# design.net
KiCad netlist of a schematic drawn in EAGLE
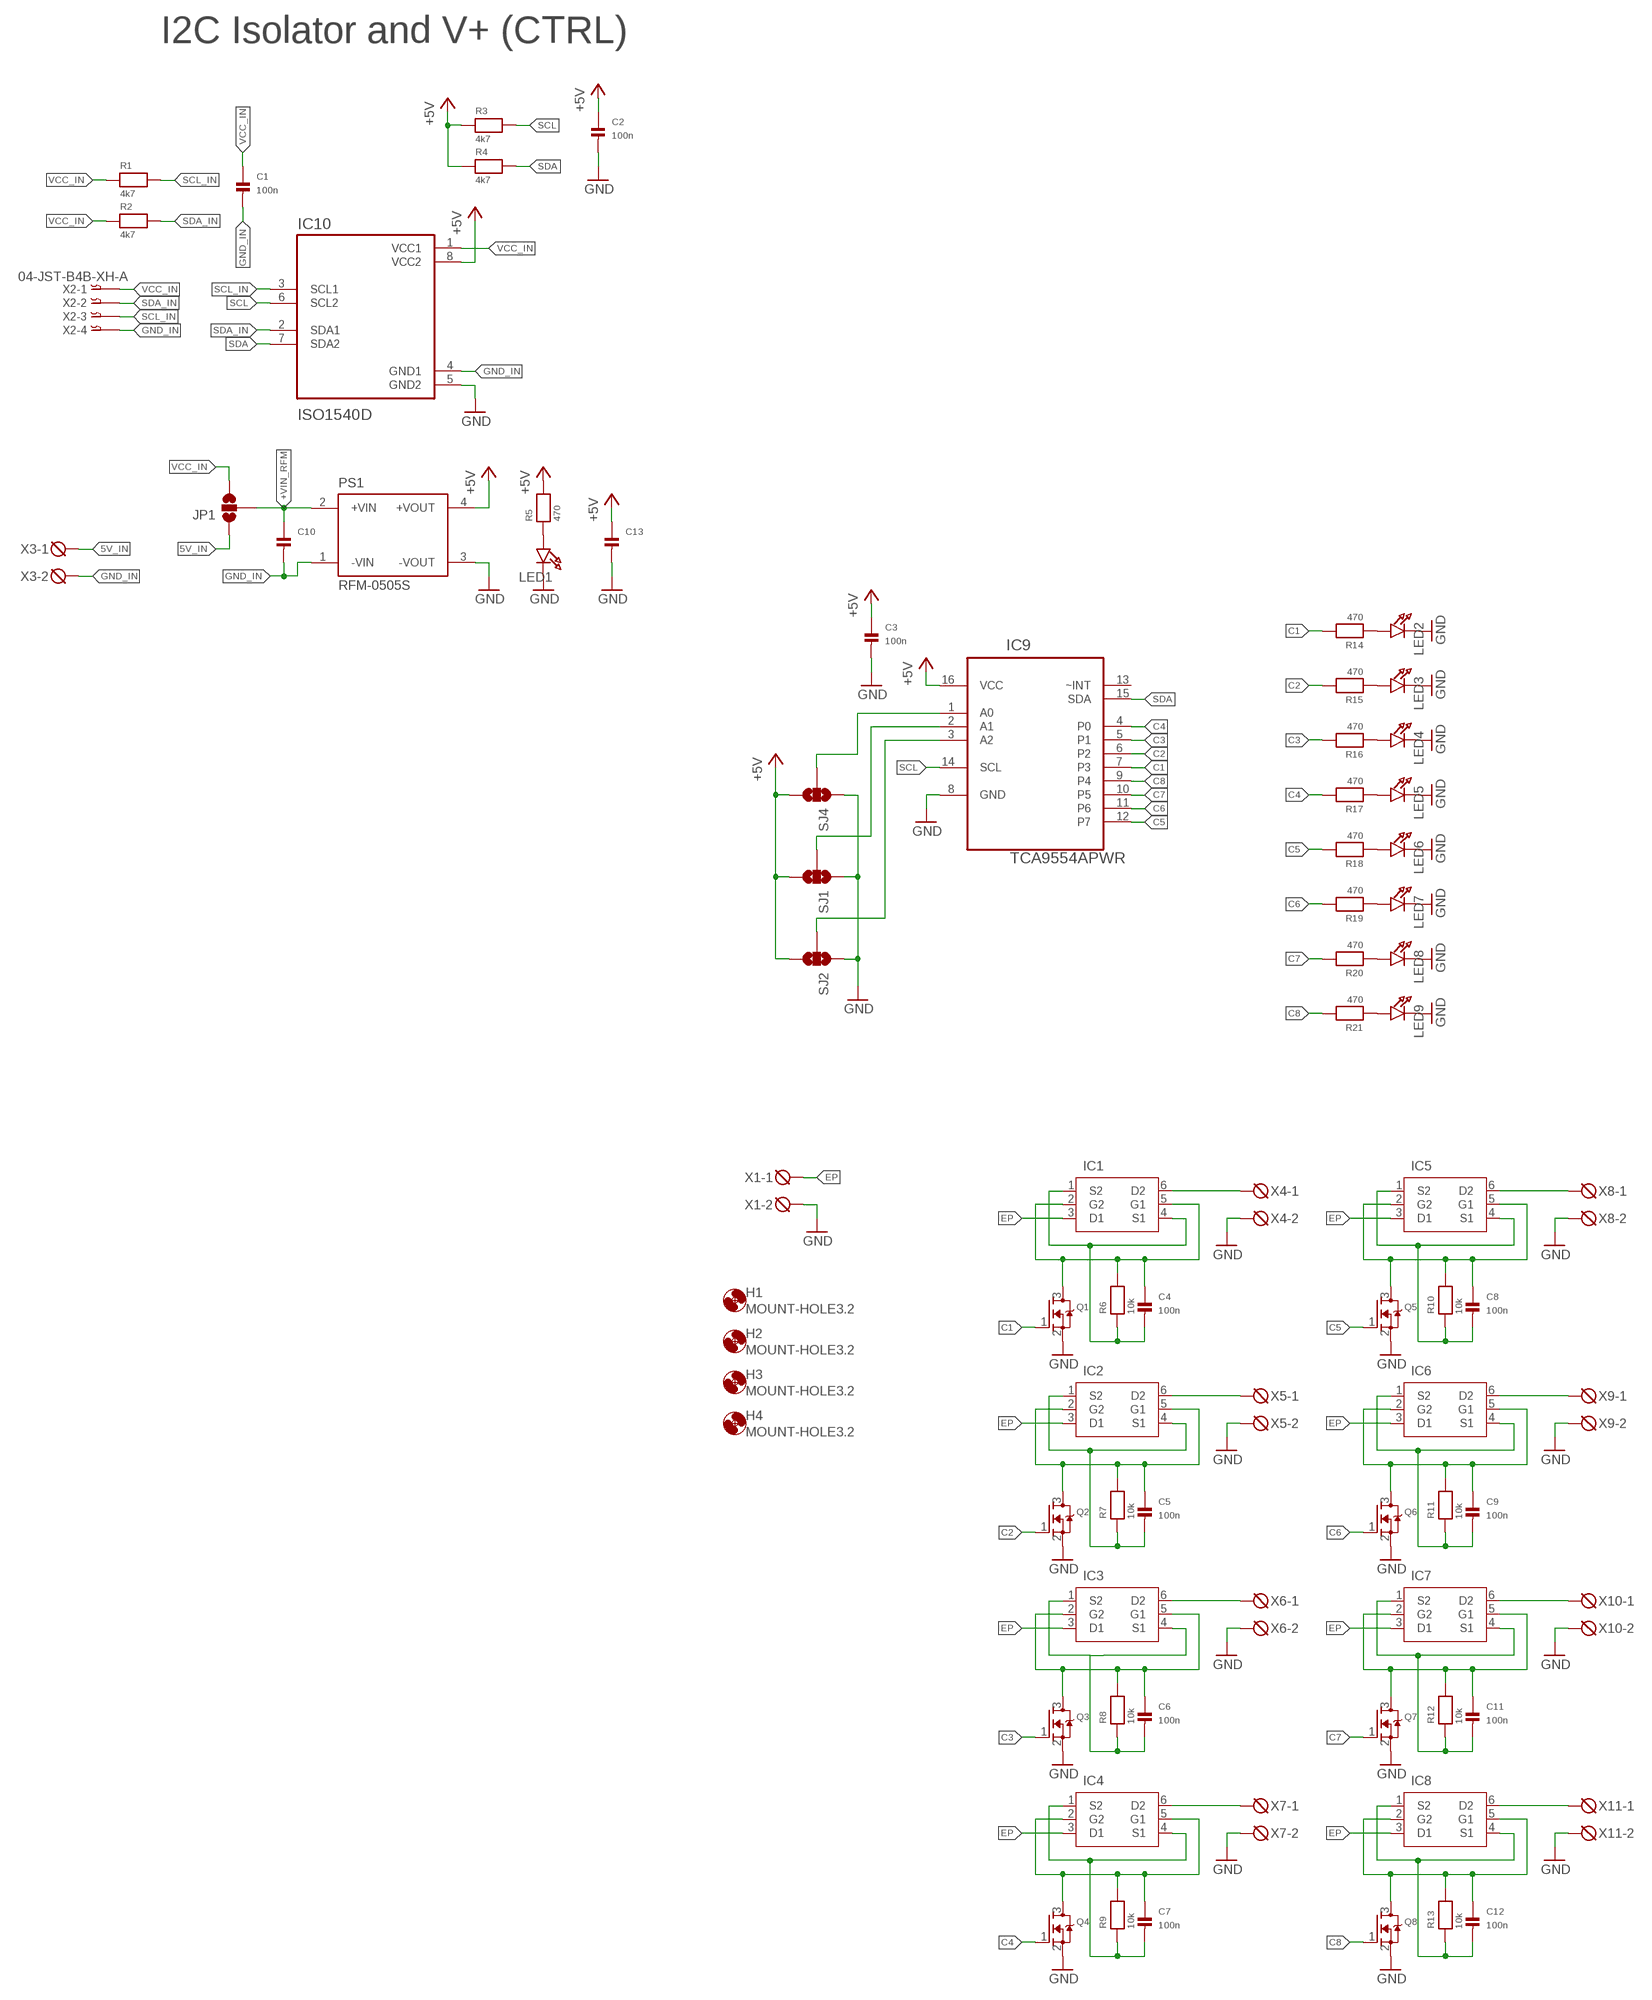
[diagram p0: schematic, sheet 1]

(export (version "E")
  (design (tool "Eeschema 10.0.6"))
  (components
    (comp (ref "C1")
      (value "100n")
      (footprint "eagle-import:0603")
      (libsource (lib "eagle-import") (part "CAP_CERAMIC0603"))
    )
    (comp (ref "C2")
      (value "100n")
      (footprint "eagle-import:0603")
      (libsource (lib "eagle-import") (part "CAP_CERAMIC0603"))
    )
    (comp (ref "C3")
      (value "100n")
      (footprint "eagle-import:0603")
      (libsource (lib "eagle-import") (part "CAP_CERAMIC0603"))
    )
    (comp (ref "C4")
      (value "100n")
      (footprint "eagle-import:0603")
      (libsource (lib "eagle-import") (part "CAP_CERAMIC0603"))
    )
    (comp (ref "C5")
      (value "100n")
      (footprint "eagle-import:0603")
      (libsource (lib "eagle-import") (part "CAP_CERAMIC0603"))
    )
    (comp (ref "C6")
      (value "100n")
      (footprint "eagle-import:0603")
      (libsource (lib "eagle-import") (part "CAP_CERAMIC0603"))
    )
    (comp (ref "C7")
      (value "100n")
      (footprint "eagle-import:0603")
      (libsource (lib "eagle-import") (part "CAP_CERAMIC0603"))
    )
    (comp (ref "C8")
      (value "100n")
      (footprint "eagle-import:0603")
      (libsource (lib "eagle-import") (part "CAP_CERAMIC0603"))
    )
    (comp (ref "C9")
      (value "100n")
      (footprint "eagle-import:0603")
      (libsource (lib "eagle-import") (part "CAP_CERAMIC0603"))
    )
    (comp (ref "C10")
      (value "CAP_CERAMIC0805")
      (footprint "eagle-import:0805")
      (libsource (lib "eagle-import") (part "CAP_CERAMIC0805"))
    )
    (comp (ref "C11")
      (value "100n")
      (footprint "eagle-import:0603")
      (libsource (lib "eagle-import") (part "CAP_CERAMIC0603"))
    )
    (comp (ref "C12")
      (value "100n")
      (footprint "eagle-import:0603")
      (libsource (lib "eagle-import") (part "CAP_CERAMIC0603"))
    )
    (comp (ref "C13")
      (value "CAP_CERAMIC0805")
      (footprint "eagle-import:0805")
      (libsource (lib "eagle-import") (part "CAP_CERAMIC0805"))
    )
    (comp (ref "H1")
      (value "MOUNT-HOLE3.2")
      (footprint "eagle-import:3,2")
      (libsource (lib "eagle-import") (part "MOUNT-HOLE3.2"))
    )
    (comp (ref "H2")
      (value "MOUNT-HOLE3.2")
      (footprint "eagle-import:3,2")
      (libsource (lib "eagle-import") (part "MOUNT-HOLE3.2"))
    )
    (comp (ref "H3")
      (value "MOUNT-HOLE3.2")
      (footprint "eagle-import:3,2")
      (libsource (lib "eagle-import") (part "MOUNT-HOLE3.2"))
    )
    (comp (ref "H4")
      (value "MOUNT-HOLE3.2")
      (footprint "eagle-import:3,2")
      (libsource (lib "eagle-import") (part "MOUNT-HOLE3.2"))
    )
    (comp (ref "IC1")
      (value "DMP2200UDW")
      (footprint "eagle-import:SOT65P210X110-6N")
      (libsource (lib "eagle-import") (part "DMP2200UDW"))
    )
    (comp (ref "IC2")
      (value "DMP2200UDW")
      (footprint "eagle-import:SOT65P210X110-6N")
      (libsource (lib "eagle-import") (part "DMP2200UDW"))
    )
    (comp (ref "IC3")
      (value "DMP2200UDW")
      (footprint "eagle-import:SOT65P210X110-6N")
      (libsource (lib "eagle-import") (part "DMP2200UDW"))
    )
    (comp (ref "IC4")
      (value "DMP2200UDW")
      (footprint "eagle-import:SOT65P210X110-6N")
      (libsource (lib "eagle-import") (part "DMP2200UDW"))
    )
    (comp (ref "IC5")
      (value "DMP2200UDW")
      (footprint "eagle-import:SOT65P210X110-6N")
      (libsource (lib "eagle-import") (part "DMP2200UDW"))
    )
    (comp (ref "IC6")
      (value "DMP2200UDW")
      (footprint "eagle-import:SOT65P210X110-6N")
      (libsource (lib "eagle-import") (part "DMP2200UDW"))
    )
    (comp (ref "IC7")
      (value "DMP2200UDW")
      (footprint "eagle-import:SOT65P210X110-6N")
      (libsource (lib "eagle-import") (part "DMP2200UDW"))
    )
    (comp (ref "IC8")
      (value "DMP2200UDW")
      (footprint "eagle-import:SOT65P210X110-6N")
      (libsource (lib "eagle-import") (part "DMP2200UDW"))
    )
    (comp (ref "IC9")
      (value "TCA9554APWR")
      (footprint "eagle-import:SOP65P640X120-16N")
      (fields (field (name "MF") "Texas Instruments"))
      (libsource (lib "eagle-import") (part "TCA9554APWR"))
    )
    (comp (ref "IC10")
      (value "ISO1540D")
      (footprint "eagle-import:SOIC127P599X175-8N")
      (fields (field (name "MF") "Texas Instruments"))
      (libsource (lib "eagle-import") (part "ISO1540D"))
    )
    (comp (ref "JP1")
      (value "JUMPER-SMT_3_NO_SILK")
      (footprint "eagle-import:SMT-JUMPER_3_NO_SILK")
      (libsource (lib "eagle-import") (part "JUMPER-SMT_3_NO_SILK"))
    )
    (comp (ref "LED1")
      (value "LED0805")
      (footprint "eagle-import:CHIPLED_0805")
      (libsource (lib "eagle-import") (part "LED0805"))
    )
    (comp (ref "LED2")
      (value "LED0805")
      (footprint "eagle-import:CHIPLED_0805")
      (libsource (lib "eagle-import") (part "LED0805"))
    )
    (comp (ref "LED3")
      (value "LED0805")
      (footprint "eagle-import:CHIPLED_0805")
      (libsource (lib "eagle-import") (part "LED0805"))
    )
    (comp (ref "LED4")
      (value "LED0805")
      (footprint "eagle-import:CHIPLED_0805")
      (libsource (lib "eagle-import") (part "LED0805"))
    )
    (comp (ref "LED5")
      (value "LED0805")
      (footprint "eagle-import:CHIPLED_0805")
      (libsource (lib "eagle-import") (part "LED0805"))
    )
    (comp (ref "LED6")
      (value "LED0805")
      (footprint "eagle-import:CHIPLED_0805")
      (libsource (lib "eagle-import") (part "LED0805"))
    )
    (comp (ref "LED7")
      (value "LED0805")
      (footprint "eagle-import:CHIPLED_0805")
      (libsource (lib "eagle-import") (part "LED0805"))
    )
    (comp (ref "LED8")
      (value "LED0805")
      (footprint "eagle-import:CHIPLED_0805")
      (libsource (lib "eagle-import") (part "LED0805"))
    )
    (comp (ref "LED9")
      (value "LED0805")
      (footprint "eagle-import:CHIPLED_0805")
      (libsource (lib "eagle-import") (part "LED0805"))
    )
    (comp (ref "PS1")
      (value "RFM-0505S")
      (footprint "eagle-import:CONV_RFM-0505S")
      (fields (field (name "MF") "Recom Power"))
      (libsource (lib "eagle-import") (part "RFM-0505S"))
    )
    (comp (ref "Q1")
      (value "MOSFET-NREFLOW")
      (footprint "eagle-import:SOT23-R")
      (libsource (lib "eagle-import") (part "MOSFET-NREFLOW"))
    )
    (comp (ref "Q2")
      (value "MOSFET-NREFLOW")
      (footprint "eagle-import:SOT23-R")
      (libsource (lib "eagle-import") (part "MOSFET-NREFLOW"))
    )
    (comp (ref "Q3")
      (value "MOSFET-NREFLOW")
      (footprint "eagle-import:SOT23-R")
      (libsource (lib "eagle-import") (part "MOSFET-NREFLOW"))
    )
    (comp (ref "Q4")
      (value "MOSFET-NREFLOW")
      (footprint "eagle-import:SOT23-R")
      (libsource (lib "eagle-import") (part "MOSFET-NREFLOW"))
    )
    (comp (ref "Q5")
      (value "MOSFET-NREFLOW")
      (footprint "eagle-import:SOT23-R")
      (libsource (lib "eagle-import") (part "MOSFET-NREFLOW"))
    )
    (comp (ref "Q6")
      (value "MOSFET-NREFLOW")
      (footprint "eagle-import:SOT23-R")
      (libsource (lib "eagle-import") (part "MOSFET-NREFLOW"))
    )
    (comp (ref "Q7")
      (value "MOSFET-NREFLOW")
      (footprint "eagle-import:SOT23-R")
      (libsource (lib "eagle-import") (part "MOSFET-NREFLOW"))
    )
    (comp (ref "Q8")
      (value "MOSFET-NREFLOW")
      (footprint "eagle-import:SOT23-R")
      (libsource (lib "eagle-import") (part "MOSFET-NREFLOW"))
    )
    (comp (ref "R1")
      (value "4k7")
      (footprint "eagle-import:0603")
      (libsource (lib "eagle-import") (part "RESISTOR0603"))
    )
    (comp (ref "R2")
      (value "4k7")
      (footprint "eagle-import:0603")
      (libsource (lib "eagle-import") (part "RESISTOR0603"))
    )
    (comp (ref "R3")
      (value "4k7")
      (footprint "eagle-import:0603")
      (libsource (lib "eagle-import") (part "RESISTOR0603"))
    )
    (comp (ref "R4")
      (value "4k7")
      (footprint "eagle-import:0603")
      (libsource (lib "eagle-import") (part "RESISTOR0603"))
    )
    (comp (ref "R5")
      (value "470")
      (footprint "eagle-import:0603")
      (libsource (lib "eagle-import") (part "RESISTOR0603"))
    )
    (comp (ref "R6")
      (value "10k")
      (footprint "eagle-import:0603")
      (libsource (lib "eagle-import") (part "RESISTOR0603"))
    )
    (comp (ref "R7")
      (value "10k")
      (footprint "eagle-import:0603")
      (libsource (lib "eagle-import") (part "RESISTOR0603"))
    )
    (comp (ref "R8")
      (value "10k")
      (footprint "eagle-import:0603")
      (libsource (lib "eagle-import") (part "RESISTOR0603"))
    )
    (comp (ref "R9")
      (value "10k")
      (footprint "eagle-import:0603")
      (libsource (lib "eagle-import") (part "RESISTOR0603"))
    )
    (comp (ref "R10")
      (value "10k")
      (footprint "eagle-import:0603")
      (libsource (lib "eagle-import") (part "RESISTOR0603"))
    )
    (comp (ref "R11")
      (value "10k")
      (footprint "eagle-import:0603")
      (libsource (lib "eagle-import") (part "RESISTOR0603"))
    )
    (comp (ref "R12")
      (value "10k")
      (footprint "eagle-import:0603")
      (libsource (lib "eagle-import") (part "RESISTOR0603"))
    )
    (comp (ref "R13")
      (value "10k")
      (footprint "eagle-import:0603")
      (libsource (lib "eagle-import") (part "RESISTOR0603"))
    )
    (comp (ref "R14")
      (value "470")
      (footprint "eagle-import:0603")
      (libsource (lib "eagle-import") (part "RESISTOR0603"))
    )
    (comp (ref "R15")
      (value "470")
      (footprint "eagle-import:0603")
      (libsource (lib "eagle-import") (part "RESISTOR0603"))
    )
    (comp (ref "R16")
      (value "470")
      (footprint "eagle-import:0603")
      (libsource (lib "eagle-import") (part "RESISTOR0603"))
    )
    (comp (ref "R17")
      (value "470")
      (footprint "eagle-import:0603")
      (libsource (lib "eagle-import") (part "RESISTOR0603"))
    )
    (comp (ref "R18")
      (value "470")
      (footprint "eagle-import:0603")
      (libsource (lib "eagle-import") (part "RESISTOR0603"))
    )
    (comp (ref "R19")
      (value "470")
      (footprint "eagle-import:0603")
      (libsource (lib "eagle-import") (part "RESISTOR0603"))
    )
    (comp (ref "R20")
      (value "470")
      (footprint "eagle-import:0603")
      (libsource (lib "eagle-import") (part "RESISTOR0603"))
    )
    (comp (ref "R21")
      (value "470")
      (footprint "eagle-import:0603")
      (libsource (lib "eagle-import") (part "RESISTOR0603"))
    )
    (comp (ref "SJ1")
      (value "SOLDERJUMPER_2WAYS")
      (footprint "eagle-import:SJ_3")
      (libsource (lib "eagle-import") (part "SOLDERJUMPER_2WAYS"))
    )
    (comp (ref "SJ2")
      (value "SOLDERJUMPER_2WAYS")
      (footprint "eagle-import:SJ_3")
      (libsource (lib "eagle-import") (part "SOLDERJUMPER_2WAYS"))
    )
    (comp (ref "SJ4")
      (value "SOLDERJUMPER_2WAYS")
      (footprint "eagle-import:SJ_3")
      (libsource (lib "eagle-import") (part "SOLDERJUMPER_2WAYS"))
    )
    (comp (ref "X1")
      (value "DG3XX-02-5.0")
      (footprint "eagle-import:DG306-5.0-02P")
      (libsource (lib "eagle-import") (part "DG3XX-02-5.0"))
    )
    (comp (ref "X2")
      (value "04-JST-B4B-XH-A")
      (footprint "eagle-import:B4B-XH")
      (libsource (lib "eagle-import") (part "04-JST-B4B-XH-A"))
    )
    (comp (ref "X3")
      (value "DG3XX-02-5.0")
      (footprint "eagle-import:DG306-5.0-02P")
      (libsource (lib "eagle-import") (part "DG3XX-02-5.0"))
    )
    (comp (ref "X4")
      (value "DG3XX-02-5.0")
      (footprint "eagle-import:DG306-5.0-02P")
      (libsource (lib "eagle-import") (part "DG3XX-02-5.0"))
    )
    (comp (ref "X5")
      (value "DG3XX-02-5.0")
      (footprint "eagle-import:DG306-5.0-02P")
      (libsource (lib "eagle-import") (part "DG3XX-02-5.0"))
    )
    (comp (ref "X6")
      (value "DG3XX-02-5.0")
      (footprint "eagle-import:DG306-5.0-02P")
      (libsource (lib "eagle-import") (part "DG3XX-02-5.0"))
    )
    (comp (ref "X7")
      (value "DG3XX-02-5.0")
      (footprint "eagle-import:DG306-5.0-02P")
      (libsource (lib "eagle-import") (part "DG3XX-02-5.0"))
    )
    (comp (ref "X8")
      (value "DG3XX-02-5.0")
      (footprint "eagle-import:DG306-5.0-02P")
      (libsource (lib "eagle-import") (part "DG3XX-02-5.0"))
    )
    (comp (ref "X9")
      (value "DG3XX-02-5.0")
      (footprint "eagle-import:DG306-5.0-02P")
      (libsource (lib "eagle-import") (part "DG3XX-02-5.0"))
    )
    (comp (ref "X10")
      (value "DG3XX-02-5.0")
      (footprint "eagle-import:DG306-5.0-02P")
      (libsource (lib "eagle-import") (part "DG3XX-02-5.0"))
    )
    (comp (ref "X11")
      (value "DG3XX-02-5.0")
      (footprint "eagle-import:DG306-5.0-02P")
      (libsource (lib "eagle-import") (part "DG3XX-02-5.0"))
    )
  )
  (nets
    (net (code "1") (name "+5V") (class "Default")
      (node (ref "C13") (pin "1") (pinfunction "P$1_1") (pintype "passive"))
      (node (ref "C2") (pin "1") (pinfunction "P$1_1") (pintype "passive"))
      (node (ref "C3") (pin "1") (pinfunction "P$1_1") (pintype "passive"))
      (node (ref "IC10") (pin "8") (pinfunction "VCC2_8") (pintype "power_in"))
      (node (ref "IC9") (pin "16") (pinfunction "VCC_16") (pintype "power_in"))
      (node (ref "PS1") (pin "4") (pinfunction "+VOUT_4") (pintype "output"))
      (node (ref "R3") (pin "1") (pinfunction "1_1") (pintype "passive"))
      (node (ref "R4") (pin "1") (pinfunction "1_1") (pintype "passive"))
      (node (ref "R5") (pin "2") (pinfunction "2_2") (pintype "passive"))
      (node (ref "SJ1") (pin "3") (pinfunction "3_3") (pintype "passive"))
      (node (ref "SJ2") (pin "3") (pinfunction "3_3") (pintype "passive"))
      (node (ref "SJ4") (pin "3") (pinfunction "3_3") (pintype "passive"))
    )
    (net (code "2") (name "+VIN_RFM") (class "Default")
      (node (ref "C10") (pin "1") (pinfunction "P$1_1") (pintype "passive"))
      (node (ref "JP1") (pin "2") (pinfunction "2_2") (pintype "passive"))
      (node (ref "PS1") (pin "2") (pinfunction "+VIN_2") (pintype "input"))
    )
    (net (code "3") (name "5V_IN") (class "Default")
      (node (ref "JP1") (pin "1") (pinfunction "1_1") (pintype "passive"))
      (node (ref "X3") (pin "1") (pinfunction "KL_1") (pintype "passive"))
    )
    (net (code "4") (name "C1") (class "Default")
      (node (ref "IC9") (pin "7") (pinfunction "P3_7") (pintype "bidirectional"))
      (node (ref "Q1") (pin "1") (pinfunction "G_1") (pintype "bidirectional"))
      (node (ref "R14") (pin "2") (pinfunction "2_2") (pintype "passive"))
    )
    (net (code "5") (name "C2") (class "Default")
      (node (ref "IC9") (pin "6") (pinfunction "P2_6") (pintype "bidirectional"))
      (node (ref "Q2") (pin "1") (pinfunction "G_1") (pintype "bidirectional"))
      (node (ref "R15") (pin "2") (pinfunction "2_2") (pintype "passive"))
    )
    (net (code "6") (name "C3") (class "Default")
      (node (ref "IC9") (pin "5") (pinfunction "P1_5") (pintype "bidirectional"))
      (node (ref "Q3") (pin "1") (pinfunction "G_1") (pintype "bidirectional"))
      (node (ref "R16") (pin "2") (pinfunction "2_2") (pintype "passive"))
    )
    (net (code "7") (name "C4") (class "Default")
      (node (ref "IC9") (pin "4") (pinfunction "P0_4") (pintype "bidirectional"))
      (node (ref "Q4") (pin "1") (pinfunction "G_1") (pintype "bidirectional"))
      (node (ref "R17") (pin "2") (pinfunction "2_2") (pintype "passive"))
    )
    (net (code "8") (name "C5") (class "Default")
      (node (ref "IC9") (pin "12") (pinfunction "P7_12") (pintype "bidirectional"))
      (node (ref "Q5") (pin "1") (pinfunction "G_1") (pintype "bidirectional"))
      (node (ref "R18") (pin "2") (pinfunction "2_2") (pintype "passive"))
    )
    (net (code "9") (name "C6") (class "Default")
      (node (ref "IC9") (pin "11") (pinfunction "P6_11") (pintype "bidirectional"))
      (node (ref "Q6") (pin "1") (pinfunction "G_1") (pintype "bidirectional"))
      (node (ref "R19") (pin "2") (pinfunction "2_2") (pintype "passive"))
    )
    (net (code "10") (name "C7") (class "Default")
      (node (ref "IC9") (pin "10") (pinfunction "P5_10") (pintype "bidirectional"))
      (node (ref "Q7") (pin "1") (pinfunction "G_1") (pintype "bidirectional"))
      (node (ref "R20") (pin "2") (pinfunction "2_2") (pintype "passive"))
    )
    (net (code "11") (name "C8") (class "Default")
      (node (ref "IC9") (pin "9") (pinfunction "P4_9") (pintype "bidirectional"))
      (node (ref "Q8") (pin "1") (pinfunction "G_1") (pintype "bidirectional"))
      (node (ref "R21") (pin "2") (pinfunction "2_2") (pintype "passive"))
    )
    (net (code "12") (name "EP") (class "Default")
      (node (ref "IC1") (pin "3") (pinfunction "D1_3") (pintype "bidirectional"))
      (node (ref "IC2") (pin "3") (pinfunction "D1_3") (pintype "bidirectional"))
      (node (ref "IC3") (pin "3") (pinfunction "D1_3") (pintype "bidirectional"))
      (node (ref "IC4") (pin "3") (pinfunction "D1_3") (pintype "bidirectional"))
      (node (ref "IC5") (pin "3") (pinfunction "D1_3") (pintype "bidirectional"))
      (node (ref "IC6") (pin "3") (pinfunction "D1_3") (pintype "bidirectional"))
      (node (ref "IC7") (pin "3") (pinfunction "D1_3") (pintype "bidirectional"))
      (node (ref "IC8") (pin "3") (pinfunction "D1_3") (pintype "bidirectional"))
      (node (ref "X1") (pin "1") (pinfunction "KL_1") (pintype "passive"))
    )
    (net (code "13") (name "GND") (class "Default")
      (node (ref "C13") (pin "2") (pinfunction "P$2_2") (pintype "passive"))
      (node (ref "C2") (pin "2") (pinfunction "P$2_2") (pintype "passive"))
      (node (ref "C3") (pin "2") (pinfunction "P$2_2") (pintype "passive"))
      (node (ref "IC10") (pin "5") (pinfunction "GND2_5") (pintype "power_in"))
      (node (ref "IC9") (pin "8") (pinfunction "GND_8") (pintype "passive"))
      (node (ref "LED1") (pin "C") (pinfunction "C_C") (pintype "passive"))
      (node (ref "LED2") (pin "C") (pinfunction "C_C") (pintype "passive"))
      (node (ref "LED3") (pin "C") (pinfunction "C_C") (pintype "passive"))
      (node (ref "LED4") (pin "C") (pinfunction "C_C") (pintype "passive"))
      (node (ref "LED5") (pin "C") (pinfunction "C_C") (pintype "passive"))
      (node (ref "LED6") (pin "C") (pinfunction "C_C") (pintype "passive"))
      (node (ref "LED7") (pin "C") (pinfunction "C_C") (pintype "passive"))
      (node (ref "LED8") (pin "C") (pinfunction "C_C") (pintype "passive"))
      (node (ref "LED9") (pin "C") (pinfunction "C_C") (pintype "passive"))
      (node (ref "PS1") (pin "3") (pinfunction "-VOUT_3") (pintype "output"))
      (node (ref "Q1") (pin "2") (pinfunction "S_2") (pintype "bidirectional"))
      (node (ref "Q2") (pin "2") (pinfunction "S_2") (pintype "bidirectional"))
      (node (ref "Q3") (pin "2") (pinfunction "S_2") (pintype "bidirectional"))
      (node (ref "Q4") (pin "2") (pinfunction "S_2") (pintype "bidirectional"))
      (node (ref "Q5") (pin "2") (pinfunction "S_2") (pintype "bidirectional"))
      (node (ref "Q6") (pin "2") (pinfunction "S_2") (pintype "bidirectional"))
      (node (ref "Q7") (pin "2") (pinfunction "S_2") (pintype "bidirectional"))
      (node (ref "Q8") (pin "2") (pinfunction "S_2") (pintype "bidirectional"))
      (node (ref "SJ1") (pin "1") (pinfunction "1_1") (pintype "passive"))
      (node (ref "SJ2") (pin "1") (pinfunction "1_1") (pintype "passive"))
      (node (ref "SJ4") (pin "1") (pinfunction "1_1") (pintype "passive"))
      (node (ref "X1") (pin "2") (pinfunction "KL_2") (pintype "passive"))
      (node (ref "X10") (pin "2") (pinfunction "KL_2") (pintype "passive"))
      (node (ref "X11") (pin "2") (pinfunction "KL_2") (pintype "passive"))
      (node (ref "X4") (pin "2") (pinfunction "KL_2") (pintype "passive"))
      (node (ref "X5") (pin "2") (pinfunction "KL_2") (pintype "passive"))
      (node (ref "X6") (pin "2") (pinfunction "KL_2") (pintype "passive"))
      (node (ref "X7") (pin "2") (pinfunction "KL_2") (pintype "passive"))
      (node (ref "X8") (pin "2") (pinfunction "KL_2") (pintype "passive"))
      (node (ref "X9") (pin "2") (pinfunction "KL_2") (pintype "passive"))
    )
    (net (code "14") (name "GND_IN") (class "Default")
      (node (ref "C1") (pin "2") (pinfunction "P$2_2") (pintype "passive"))
      (node (ref "C10") (pin "2") (pinfunction "P$2_2") (pintype "passive"))
      (node (ref "IC10") (pin "4") (pinfunction "GND1_4") (pintype "power_in"))
      (node (ref "PS1") (pin "1") (pinfunction "-VIN_1") (pintype "input"))
      (node (ref "X2") (pin "P$4") (pinfunction "1_P$4") (pintype "passive"))
      (node (ref "X3") (pin "2") (pinfunction "KL_2") (pintype "passive"))
    )
    (net (code "15") (name "Net-(C4-P$1)") (class "Default")
      (node (ref "C4") (pin "1") (pinfunction "P$1_1") (pintype "passive"))
      (node (ref "IC1") (pin "2") (pinfunction "G2_2") (pintype "bidirectional"))
      (node (ref "IC1") (pin "5") (pinfunction "G1_5") (pintype "bidirectional"))
      (node (ref "Q1") (pin "3") (pinfunction "D_3") (pintype "bidirectional"))
      (node (ref "R6") (pin "2") (pinfunction "2_2") (pintype "passive"))
    )
    (net (code "16") (name "Net-(C4-P$2)") (class "Default")
      (node (ref "C4") (pin "2") (pinfunction "P$2_2") (pintype "passive"))
      (node (ref "IC1") (pin "1") (pinfunction "S2_1") (pintype "bidirectional"))
      (node (ref "IC1") (pin "4") (pinfunction "S1_4") (pintype "bidirectional"))
      (node (ref "R6") (pin "1") (pinfunction "1_1") (pintype "passive"))
    )
    (net (code "17") (name "Net-(C5-P$1)") (class "Default")
      (node (ref "C5") (pin "1") (pinfunction "P$1_1") (pintype "passive"))
      (node (ref "IC2") (pin "2") (pinfunction "G2_2") (pintype "bidirectional"))
      (node (ref "IC2") (pin "5") (pinfunction "G1_5") (pintype "bidirectional"))
      (node (ref "Q2") (pin "3") (pinfunction "D_3") (pintype "bidirectional"))
      (node (ref "R7") (pin "2") (pinfunction "2_2") (pintype "passive"))
    )
    (net (code "18") (name "Net-(C5-P$2)") (class "Default")
      (node (ref "C5") (pin "2") (pinfunction "P$2_2") (pintype "passive"))
      (node (ref "IC2") (pin "1") (pinfunction "S2_1") (pintype "bidirectional"))
      (node (ref "IC2") (pin "4") (pinfunction "S1_4") (pintype "bidirectional"))
      (node (ref "R7") (pin "1") (pinfunction "1_1") (pintype "passive"))
    )
    (net (code "19") (name "Net-(C6-P$1)") (class "Default")
      (node (ref "C6") (pin "1") (pinfunction "P$1_1") (pintype "passive"))
      (node (ref "IC3") (pin "2") (pinfunction "G2_2") (pintype "bidirectional"))
      (node (ref "IC3") (pin "5") (pinfunction "G1_5") (pintype "bidirectional"))
      (node (ref "Q3") (pin "3") (pinfunction "D_3") (pintype "bidirectional"))
      (node (ref "R8") (pin "2") (pinfunction "2_2") (pintype "passive"))
    )
    (net (code "20") (name "Net-(C6-P$2)") (class "Default")
      (node (ref "C6") (pin "2") (pinfunction "P$2_2") (pintype "passive"))
      (node (ref "IC3") (pin "1") (pinfunction "S2_1") (pintype "bidirectional"))
      (node (ref "IC3") (pin "4") (pinfunction "S1_4") (pintype "bidirectional"))
      (node (ref "R8") (pin "1") (pinfunction "1_1") (pintype "passive"))
    )
    (net (code "21") (name "Net-(C7-P$1)") (class "Default")
      (node (ref "C7") (pin "1") (pinfunction "P$1_1") (pintype "passive"))
      (node (ref "IC4") (pin "2") (pinfunction "G2_2") (pintype "bidirectional"))
      (node (ref "IC4") (pin "5") (pinfunction "G1_5") (pintype "bidirectional"))
      (node (ref "Q4") (pin "3") (pinfunction "D_3") (pintype "bidirectional"))
      (node (ref "R9") (pin "2") (pinfunction "2_2") (pintype "passive"))
    )
    (net (code "22") (name "Net-(C7-P$2)") (class "Default")
      (node (ref "C7") (pin "2") (pinfunction "P$2_2") (pintype "passive"))
      (node (ref "IC4") (pin "1") (pinfunction "S2_1") (pintype "bidirectional"))
      (node (ref "IC4") (pin "4") (pinfunction "S1_4") (pintype "bidirectional"))
      (node (ref "R9") (pin "1") (pinfunction "1_1") (pintype "passive"))
    )
    (net (code "23") (name "Net-(C8-P$1)") (class "Default")
      (node (ref "C8") (pin "1") (pinfunction "P$1_1") (pintype "passive"))
      (node (ref "IC5") (pin "2") (pinfunction "G2_2") (pintype "bidirectional"))
      (node (ref "IC5") (pin "5") (pinfunction "G1_5") (pintype "bidirectional"))
      (node (ref "Q5") (pin "3") (pinfunction "D_3") (pintype "bidirectional"))
      (node (ref "R10") (pin "2") (pinfunction "2_2") (pintype "passive"))
    )
    (net (code "24") (name "Net-(C8-P$2)") (class "Default")
      (node (ref "C8") (pin "2") (pinfunction "P$2_2") (pintype "passive"))
      (node (ref "IC5") (pin "1") (pinfunction "S2_1") (pintype "bidirectional"))
      (node (ref "IC5") (pin "4") (pinfunction "S1_4") (pintype "bidirectional"))
      (node (ref "R10") (pin "1") (pinfunction "1_1") (pintype "passive"))
    )
    (net (code "25") (name "Net-(C9-P$1)") (class "Default")
      (node (ref "C9") (pin "1") (pinfunction "P$1_1") (pintype "passive"))
      (node (ref "IC6") (pin "2") (pinfunction "G2_2") (pintype "bidirectional"))
      (node (ref "IC6") (pin "5") (pinfunction "G1_5") (pintype "bidirectional"))
      (node (ref "Q6") (pin "3") (pinfunction "D_3") (pintype "bidirectional"))
      (node (ref "R11") (pin "2") (pinfunction "2_2") (pintype "passive"))
    )
    (net (code "26") (name "Net-(C9-P$2)") (class "Default")
      (node (ref "C9") (pin "2") (pinfunction "P$2_2") (pintype "passive"))
      (node (ref "IC6") (pin "1") (pinfunction "S2_1") (pintype "bidirectional"))
      (node (ref "IC6") (pin "4") (pinfunction "S1_4") (pintype "bidirectional"))
      (node (ref "R11") (pin "1") (pinfunction "1_1") (pintype "passive"))
    )
    (net (code "27") (name "Net-(C11-P$1)") (class "Default")
      (node (ref "C11") (pin "1") (pinfunction "P$1_1") (pintype "passive"))
      (node (ref "IC7") (pin "2") (pinfunction "G2_2") (pintype "bidirectional"))
      (node (ref "IC7") (pin "5") (pinfunction "G1_5") (pintype "bidirectional"))
      (node (ref "Q7") (pin "3") (pinfunction "D_3") (pintype "bidirectional"))
      (node (ref "R12") (pin "2") (pinfunction "2_2") (pintype "passive"))
    )
    (net (code "28") (name "Net-(C11-P$2)") (class "Default")
      (node (ref "C11") (pin "2") (pinfunction "P$2_2") (pintype "passive"))
      (node (ref "IC7") (pin "1") (pinfunction "S2_1") (pintype "bidirectional"))
      (node (ref "IC7") (pin "4") (pinfunction "S1_4") (pintype "bidirectional"))
      (node (ref "R12") (pin "1") (pinfunction "1_1") (pintype "passive"))
    )
    (net (code "29") (name "Net-(C12-P$1)") (class "Default")
      (node (ref "C12") (pin "1") (pinfunction "P$1_1") (pintype "passive"))
      (node (ref "IC8") (pin "2") (pinfunction "G2_2") (pintype "bidirectional"))
      (node (ref "IC8") (pin "5") (pinfunction "G1_5") (pintype "bidirectional"))
      (node (ref "Q8") (pin "3") (pinfunction "D_3") (pintype "bidirectional"))
      (node (ref "R13") (pin "2") (pinfunction "2_2") (pintype "passive"))
    )
    (net (code "30") (name "Net-(C12-P$2)") (class "Default")
      (node (ref "C12") (pin "2") (pinfunction "P$2_2") (pintype "passive"))
      (node (ref "IC8") (pin "1") (pinfunction "S2_1") (pintype "bidirectional"))
      (node (ref "IC8") (pin "4") (pinfunction "S1_4") (pintype "bidirectional"))
      (node (ref "R13") (pin "1") (pinfunction "1_1") (pintype "passive"))
    )
    (net (code "31") (name "Net-(IC1-D2)") (class "Default")
      (node (ref "IC1") (pin "6") (pinfunction "D2_6") (pintype "bidirectional"))
      (node (ref "X4") (pin "1") (pinfunction "KL_1") (pintype "passive"))
    )
    (net (code "32") (name "Net-(IC2-D2)") (class "Default")
      (node (ref "IC2") (pin "6") (pinfunction "D2_6") (pintype "bidirectional"))
      (node (ref "X5") (pin "1") (pinfunction "KL_1") (pintype "passive"))
    )
    (net (code "33") (name "Net-(IC3-D2)") (class "Default")
      (node (ref "IC3") (pin "6") (pinfunction "D2_6") (pintype "bidirectional"))
      (node (ref "X6") (pin "1") (pinfunction "KL_1") (pintype "passive"))
    )
    (net (code "34") (name "Net-(IC4-D2)") (class "Default")
      (node (ref "IC4") (pin "6") (pinfunction "D2_6") (pintype "bidirectional"))
      (node (ref "X7") (pin "1") (pinfunction "KL_1") (pintype "passive"))
    )
    (net (code "35") (name "Net-(IC5-D2)") (class "Default")
      (node (ref "IC5") (pin "6") (pinfunction "D2_6") (pintype "bidirectional"))
      (node (ref "X8") (pin "1") (pinfunction "KL_1") (pintype "passive"))
    )
    (net (code "36") (name "Net-(IC6-D2)") (class "Default")
      (node (ref "IC6") (pin "6") (pinfunction "D2_6") (pintype "bidirectional"))
      (node (ref "X9") (pin "1") (pinfunction "KL_1") (pintype "passive"))
    )
    (net (code "37") (name "Net-(IC7-D2)") (class "Default")
      (node (ref "IC7") (pin "6") (pinfunction "D2_6") (pintype "bidirectional"))
      (node (ref "X10") (pin "1") (pinfunction "KL_1") (pintype "passive"))
    )
    (net (code "38") (name "Net-(IC8-D2)") (class "Default")
      (node (ref "IC8") (pin "6") (pinfunction "D2_6") (pintype "bidirectional"))
      (node (ref "X11") (pin "1") (pinfunction "KL_1") (pintype "passive"))
    )
    (net (code "39") (name "Net-(IC9-A0)") (class "Default")
      (node (ref "IC9") (pin "1") (pinfunction "A0_1") (pintype "input"))
      (node (ref "SJ4") (pin "2") (pinfunction "2_2") (pintype "passive"))
    )
    (net (code "40") (name "Net-(IC9-A1)") (class "Default")
      (node (ref "IC9") (pin "2") (pinfunction "A1_2") (pintype "input"))
      (node (ref "SJ1") (pin "2") (pinfunction "2_2") (pintype "passive"))
    )
    (net (code "41") (name "Net-(IC9-A2)") (class "Default")
      (node (ref "IC9") (pin "3") (pinfunction "A2_3") (pintype "input"))
      (node (ref "SJ2") (pin "2") (pinfunction "2_2") (pintype "passive"))
    )
    (net (code "42") (name "Net-(LED1-PadA)") (class "Default")
      (node (ref "LED1") (pin "A") (pinfunction "A_A") (pintype "passive"))
      (node (ref "R5") (pin "1") (pinfunction "1_1") (pintype "passive"))
    )
    (net (code "43") (name "Net-(LED2-PadA)") (class "Default")
      (node (ref "LED2") (pin "A") (pinfunction "A_A") (pintype "passive"))
      (node (ref "R14") (pin "1") (pinfunction "1_1") (pintype "passive"))
    )
    (net (code "44") (name "Net-(LED3-PadA)") (class "Default")
      (node (ref "LED3") (pin "A") (pinfunction "A_A") (pintype "passive"))
      (node (ref "R15") (pin "1") (pinfunction "1_1") (pintype "passive"))
    )
    (net (code "45") (name "Net-(LED4-PadA)") (class "Default")
      (node (ref "LED4") (pin "A") (pinfunction "A_A") (pintype "passive"))
      (node (ref "R16") (pin "1") (pinfunction "1_1") (pintype "passive"))
    )
    (net (code "46") (name "Net-(LED5-PadA)") (class "Default")
      (node (ref "LED5") (pin "A") (pinfunction "A_A") (pintype "passive"))
      (node (ref "R17") (pin "1") (pinfunction "1_1") (pintype "passive"))
    )
    (net (code "47") (name "Net-(LED6-PadA)") (class "Default")
      (node (ref "LED6") (pin "A") (pinfunction "A_A") (pintype "passive"))
      (node (ref "R18") (pin "1") (pinfunction "1_1") (pintype "passive"))
    )
    (net (code "48") (name "Net-(LED7-PadA)") (class "Default")
      (node (ref "LED7") (pin "A") (pinfunction "A_A") (pintype "passive"))
      (node (ref "R19") (pin "1") (pinfunction "1_1") (pintype "passive"))
    )
    (net (code "49") (name "Net-(LED8-PadA)") (class "Default")
      (node (ref "LED8") (pin "A") (pinfunction "A_A") (pintype "passive"))
      (node (ref "R20") (pin "1") (pinfunction "1_1") (pintype "passive"))
    )
    (net (code "50") (name "Net-(LED9-PadA)") (class "Default")
      (node (ref "LED9") (pin "A") (pinfunction "A_A") (pintype "passive"))
      (node (ref "R21") (pin "1") (pinfunction "1_1") (pintype "passive"))
    )
    (net (code "51") (name "SCL") (class "Default")
      (node (ref "IC10") (pin "6") (pinfunction "SCL2_6") (pintype "input"))
      (node (ref "IC9") (pin "14") (pinfunction "SCL_14") (pintype "input"))
      (node (ref "R3") (pin "2") (pinfunction "2_2") (pintype "passive"))
    )
    (net (code "52") (name "SCL_IN") (class "Default")
      (node (ref "IC10") (pin "3") (pinfunction "SCL1_3") (pintype "input"))
      (node (ref "R1") (pin "2") (pinfunction "2_2") (pintype "passive"))
      (node (ref "X2") (pin "P$3") (pinfunction "1_P$3") (pintype "passive"))
    )
    (net (code "53") (name "SDA") (class "Default")
      (node (ref "IC10") (pin "7") (pinfunction "SDA2_7") (pintype "bidirectional"))
      (node (ref "IC9") (pin "15") (pinfunction "SDA_15") (pintype "bidirectional"))
      (node (ref "R4") (pin "2") (pinfunction "2_2") (pintype "passive"))
    )
    (net (code "54") (name "SDA_IN") (class "Default")
      (node (ref "IC10") (pin "2") (pinfunction "SDA1_2") (pintype "bidirectional"))
      (node (ref "R2") (pin "2") (pinfunction "2_2") (pintype "passive"))
      (node (ref "X2") (pin "P$2") (pinfunction "1_P$2") (pintype "passive"))
    )
    (net (code "55") (name "VCC_IN") (class "Default")
      (node (ref "C1") (pin "1") (pinfunction "P$1_1") (pintype "passive"))
      (node (ref "IC10") (pin "1") (pinfunction "VCC1_1") (pintype "power_in"))
      (node (ref "JP1") (pin "3") (pinfunction "3_3") (pintype "passive"))
      (node (ref "R1") (pin "1") (pinfunction "1_1") (pintype "passive"))
      (node (ref "R2") (pin "1") (pinfunction "1_1") (pintype "passive"))
      (node (ref "X2") (pin "P$1") (pinfunction "1_P$1") (pintype "passive"))
    )
    (net (code "56") (name "unconnected-(IC9-~{INT}-Pad13)") (class "Default")
      (node (ref "IC9") (pin "13") (pinfunction "~{INT}_13") (pintype "output"))
    )
  )
)
